# Horn_Board.net
KiCad netlist of a schematic drawn in EAGLE
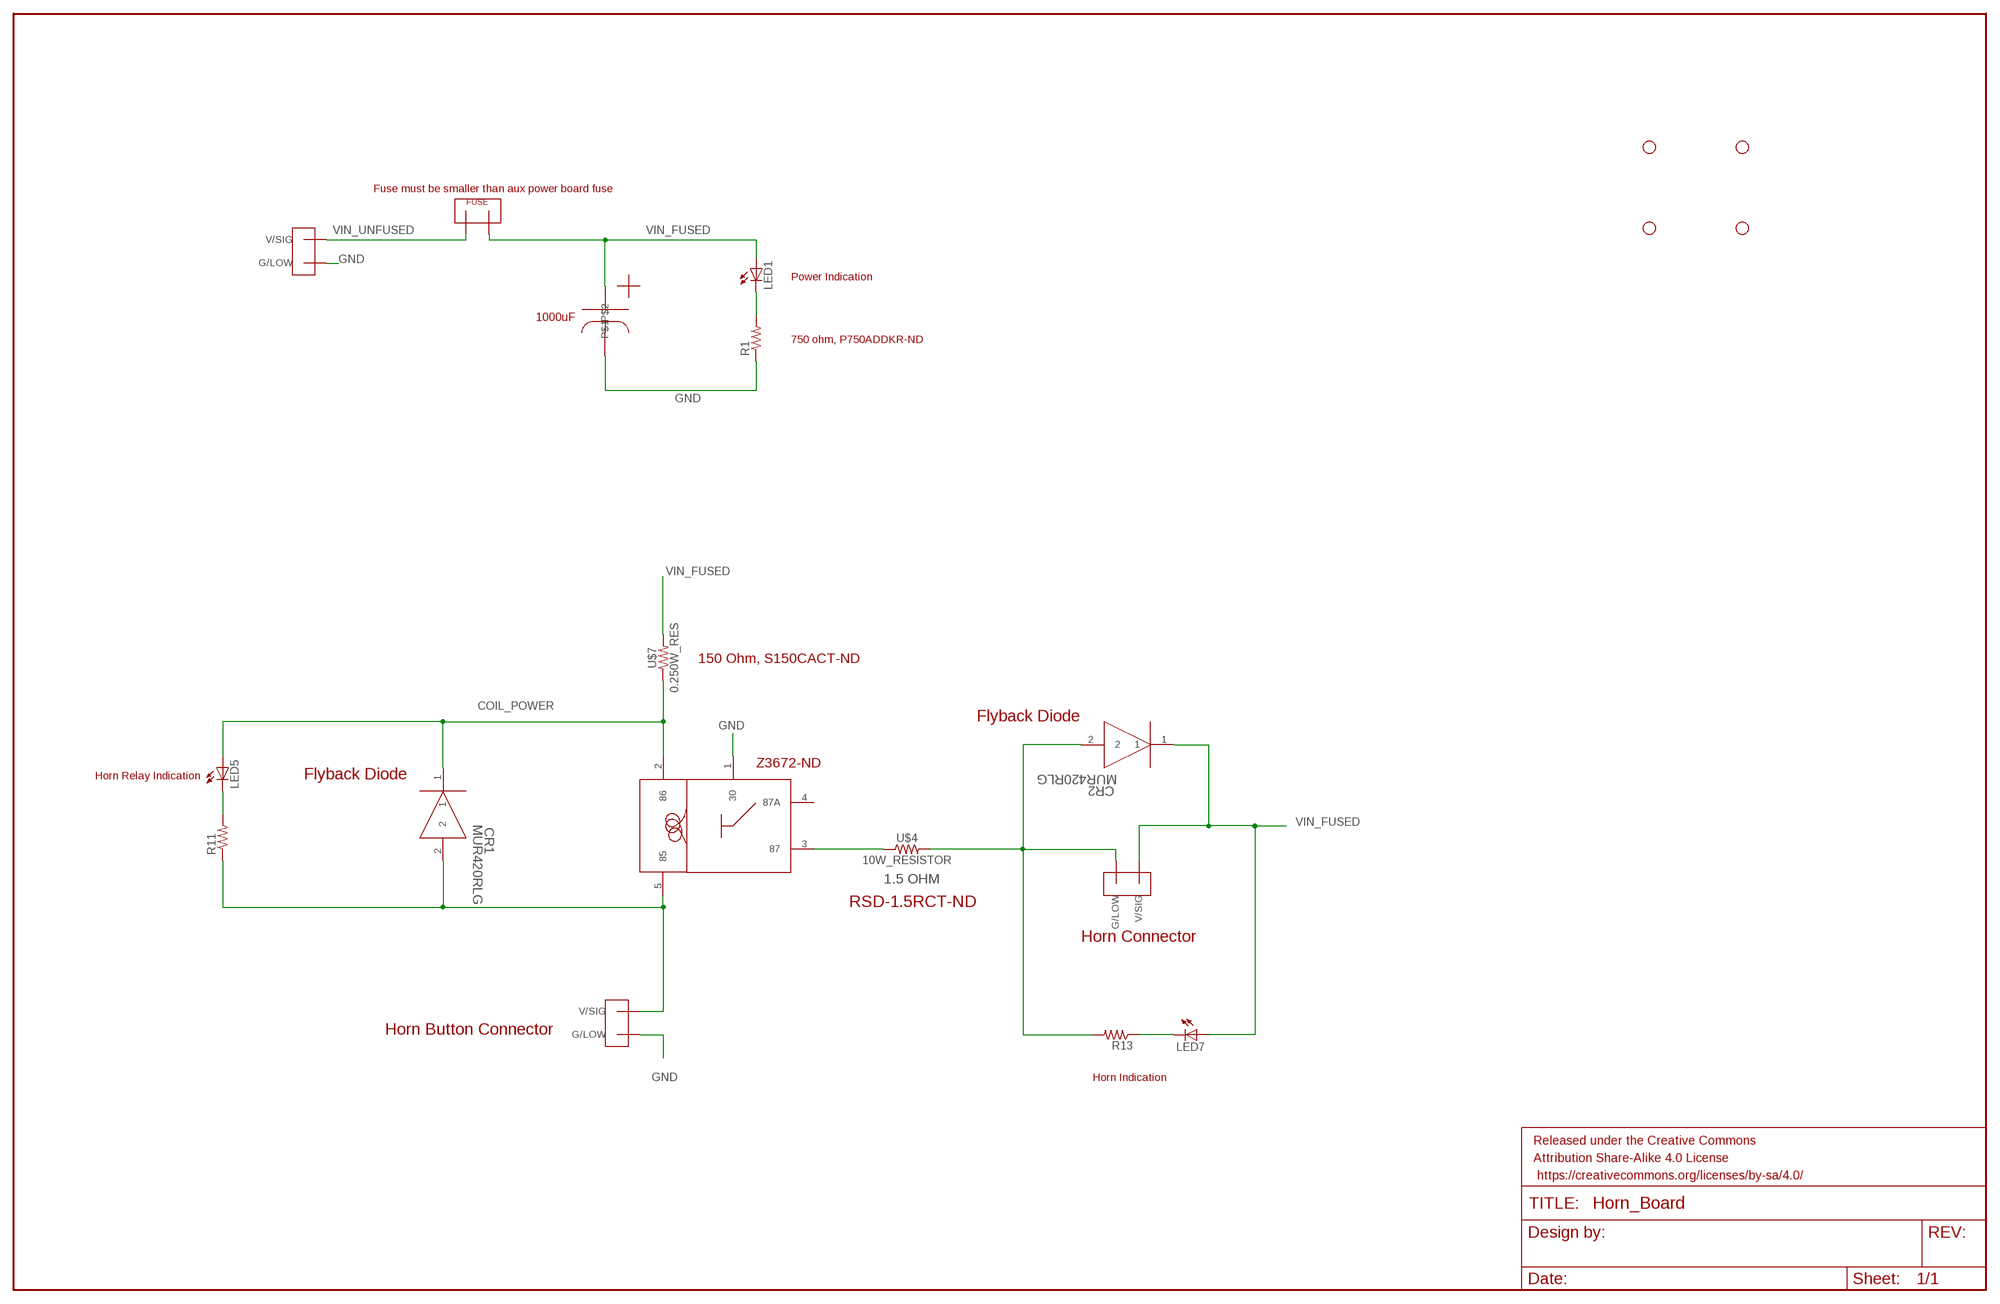
[diagram p0: schematic, sheet 1]

(export (version "E")
  (design (tool "Eeschema 10.0.6"))
  (components
    (comp (ref "CR1")
      (value "MUR420RLG")
      (footprint "eagle-import:DO-201AD")
      (libsource (lib "eagle-import") (part "MUR420RLG"))
    )
    (comp (ref "CR2")
      (value "MUR420RLG")
      (footprint "eagle-import:DO-201AD")
      (libsource (lib "eagle-import") (part "MUR420RLG"))
    )
    (comp (ref "FRAME1")
      (value "FRAME-LEDGER")
      (footprint "eagle-import:CREATIVE_COMMONS")
      (libsource (lib "eagle-import") (part "FRAME-LEDGER"))
    )
    (comp (ref "H1")
      (value "STAND-OFF")
      (footprint "eagle-import:STAND-OFF")
      (libsource (lib "eagle-import") (part "STAND-OFF"))
    )
    (comp (ref "H2")
      (value "STAND-OFF")
      (footprint "eagle-import:STAND-OFF")
      (libsource (lib "eagle-import") (part "STAND-OFF"))
    )
    (comp (ref "H3")
      (value "STAND-OFF")
      (footprint "eagle-import:STAND-OFF")
      (libsource (lib "eagle-import") (part "STAND-OFF"))
    )
    (comp (ref "H4")
      (value "STAND-OFF")
      (footprint "eagle-import:STAND-OFF")
      (libsource (lib "eagle-import") (part "STAND-OFF"))
    )
    (comp (ref "LED1")
      (value "LEDCHIP-LED0805")
      (footprint "eagle-import:CHIP-LED0805")
      (libsource (lib "eagle-import") (part "LEDCHIP-LED0805"))
    )
    (comp (ref "LED5")
      (value "LEDCHIP-LED0805")
      (footprint "eagle-import:CHIP-LED0805")
      (libsource (lib "eagle-import") (part "LEDCHIP-LED0805"))
    )
    (comp (ref "LED7")
      (value "LEDCHIP-LED0805")
      (footprint "eagle-import:CHIP-LED0805")
      (libsource (lib "eagle-import") (part "LEDCHIP-LED0805"))
    )
    (comp (ref "R1")
      (value "R-US_M0805")
      (footprint "eagle-import:M0805")
      (libsource (lib "eagle-import") (part "R-US_M0805"))
    )
    (comp (ref "R11")
      (value "R-US_M0805")
      (footprint "eagle-import:M0805")
      (libsource (lib "eagle-import") (part "R-US_M0805"))
    )
    (comp (ref "R13")
      (value "R-US_M0805")
      (footprint "eagle-import:M0805")
      (libsource (lib "eagle-import") (part "R-US_M0805"))
    )
    (comp (ref "U$1")
      (value "TE770966")
      (footprint "eagle-import:2X1-MATE-N-LOCK")
      (libsource (lib "eagle-import") (part "TE770966"))
    )
    (comp (ref "U$2")
      (value "FUSEMINI-BLADE")
      (footprint "eagle-import:MINI-BLADE-FUSE")
      (libsource (lib "eagle-import") (part "FUSEMINI-BLADE"))
    )
    (comp (ref "U$3")
      (value "OMRON_G5LE-1")
      (footprint "eagle-import:OMRON_G5LE-1")
      (libsource (lib "eagle-import") (part "OMRON_G5LE-1"))
    )
    (comp (ref "U$4")
      (value "10W_RESISTOR")
      (footprint "eagle-import:10W_RESISTOR")
      (libsource (lib "eagle-import") (part "10W_RESISTOR"))
    )
    (comp (ref "U$7")
      (value "0.250W_RES")
      (footprint "eagle-import:AXIAL-0.3")
      (libsource (lib "eagle-import") (part "0.250W_RES"))
    )
    (comp (ref "U$17")
      (value "TE770966")
      (footprint "eagle-import:2X1-MATE-N-LOCK")
      (libsource (lib "eagle-import") (part "TE770966"))
    )
    (comp (ref "U$18")
      (value "TE770966")
      (footprint "eagle-import:2X1-MATE-N-LOCK")
      (libsource (lib "eagle-import") (part "TE770966"))
    )
    (comp (ref "U$22")
      (value "CAPESK108M025AH4EA")
      (footprint "eagle-import:ESK108M025AH4EA")
      (libsource (lib "eagle-import") (part "CAPESK108M025AH4EA"))
    )
  )
  (nets
    (net (code "1") (name "/COIL_POWER") (class "Default")
      (node (ref "CR1") (pin "1") (pinfunction "1_1") (pintype "passive"))
      (node (ref "LED5") (pin "A") (pinfunction "A_A") (pintype "passive"))
      (node (ref "U$3") (pin "2") (pinfunction "86_2") (pintype "bidirectional"))
      (node (ref "U$7") (pin "P$1") (pinfunction "1_P$1") (pintype "passive"))
    )
    (net (code "2") (name "/GND") (class "Default")
      (node (ref "R1") (pin "1") (pinfunction "1_1") (pintype "passive"))
      (node (ref "U$1") (pin "CIRCUIT2") (pinfunction "G/LOW_CIRCUIT2") (pintype "bidirectional"))
      (node (ref "U$17") (pin "CIRCUIT2") (pinfunction "G/LOW_CIRCUIT2") (pintype "bidirectional"))
      (node (ref "U$22") (pin "P$2") (pinfunction "P$2_P$2") (pintype "bidirectional"))
      (node (ref "U$3") (pin "1") (pinfunction "30_1") (pintype "bidirectional"))
    )
    (net (code "3") (name "/VIN_FUSED") (class "Default")
      (node (ref "CR2") (pin "1") (pinfunction "1_1") (pintype "passive"))
      (node (ref "LED1") (pin "A") (pinfunction "A_A") (pintype "passive"))
      (node (ref "LED7") (pin "A") (pinfunction "A_A") (pintype "passive"))
      (node (ref "U$18") (pin "CIRCUIT1") (pinfunction "V/SIG_CIRCUIT1") (pintype "bidirectional"))
      (node (ref "U$2") (pin "OUT") (pinfunction "OUT_OUT") (pintype "bidirectional"))
      (node (ref "U$22") (pin "P$1") (pinfunction "P$1_P$1") (pintype "bidirectional"))
      (node (ref "U$7") (pin "P$2") (pinfunction "2_P$2") (pintype "passive"))
    )
    (net (code "4") (name "/VIN_UNFUSED") (class "Default")
      (node (ref "U$1") (pin "CIRCUIT1") (pinfunction "V/SIG_CIRCUIT1") (pintype "bidirectional"))
      (node (ref "U$2") (pin "IN") (pinfunction "IN_IN") (pintype "bidirectional"))
    )
    (net (code "5") (name "Net-(LED1-PadC)") (class "Default")
      (node (ref "LED1") (pin "C") (pinfunction "C_C") (pintype "passive"))
      (node (ref "R1") (pin "2") (pinfunction "2_2") (pintype "passive"))
    )
    (net (code "6") (name "Net-(LED5-PadC)") (class "Default")
      (node (ref "LED5") (pin "C") (pinfunction "C_C") (pintype "passive"))
      (node (ref "R11") (pin "2") (pinfunction "2_2") (pintype "passive"))
    )
    (net (code "7") (name "Net-(LED7-PadC)") (class "Default")
      (node (ref "LED7") (pin "C") (pinfunction "C_C") (pintype "passive"))
      (node (ref "R13") (pin "1") (pinfunction "1_1") (pintype "passive"))
    )
    (net (code "8") (name "Net-(U$3-87)") (class "Default")
      (node (ref "U$3") (pin "3") (pinfunction "87_3") (pintype "bidirectional"))
      (node (ref "U$4") (pin "P$1") (pinfunction "1_P$1") (pintype "passive"))
    )
    (net (code "9") (name "Net-(U$17-V{slash}SIG)") (class "Default")
      (node (ref "CR1") (pin "2") (pinfunction "2_2") (pintype "passive"))
      (node (ref "R11") (pin "1") (pinfunction "1_1") (pintype "passive"))
      (node (ref "U$17") (pin "CIRCUIT1") (pinfunction "V/SIG_CIRCUIT1") (pintype "bidirectional"))
      (node (ref "U$3") (pin "5") (pinfunction "85_5") (pintype "bidirectional"))
    )
    (net (code "10") (name "Net-(U$18-G{slash}LOW)") (class "Default")
      (node (ref "CR2") (pin "2") (pinfunction "2_2") (pintype "passive"))
      (node (ref "R13") (pin "2") (pinfunction "2_2") (pintype "passive"))
      (node (ref "U$18") (pin "CIRCUIT2") (pinfunction "G/LOW_CIRCUIT2") (pintype "bidirectional"))
      (node (ref "U$4") (pin "P$2") (pinfunction "2_P$2") (pintype "passive"))
    )
    (net (code "11") (name "unconnected-(U$3-87A-Pad4)") (class "Default")
      (node (ref "U$3") (pin "4") (pinfunction "87A_4") (pintype "bidirectional"))
    )
  )
)
